# nixie_test_v1.net
KiCad netlist of a schematic drawn in EAGLE
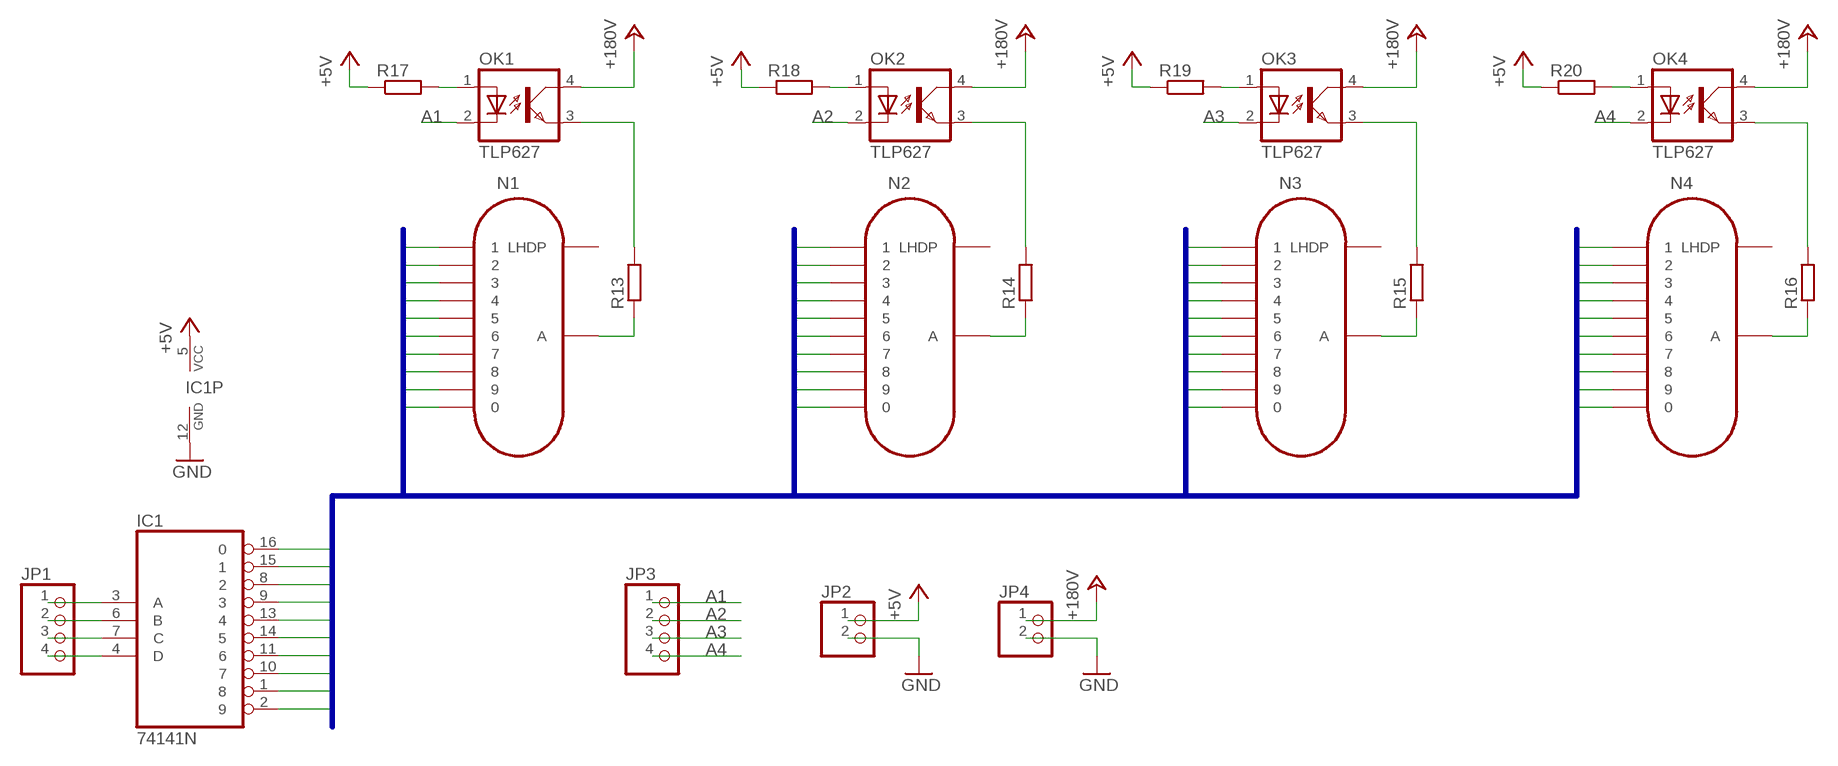
[diagram p0: schematic, sheet 1]

(export (version "E")
  (design (tool "Eeschema 10.0.6"))
  (components
    (comp (ref "IC1")
      (value "74141N")
      (footprint "eagle-import:DIL16")
      (libsource (lib "eagle-import") (part "74141N"))
    )
    (comp (ref "JP1")
      (value "PINHD-1X4")
      (footprint "eagle-import:1X04")
      (libsource (lib "eagle-import") (part "PINHD-1X4"))
    )
    (comp (ref "JP2")
      (value "PINHD-1X2")
      (footprint "eagle-import:1X02")
      (libsource (lib "eagle-import") (part "PINHD-1X2"))
    )
    (comp (ref "JP3")
      (value "PINHD-1X4")
      (footprint "eagle-import:1X04")
      (libsource (lib "eagle-import") (part "PINHD-1X4"))
    )
    (comp (ref "JP4")
      (value "PINHD-1X2")
      (footprint "eagle-import:1X02")
      (libsource (lib "eagle-import") (part "PINHD-1X2"))
    )
    (comp (ref "N1")
      (value "IN-12B")
      (footprint "eagle-import:IN-12")
      (libsource (lib "eagle-import") (part "IN-12B"))
    )
    (comp (ref "N2")
      (value "IN-12B")
      (footprint "eagle-import:IN-12")
      (libsource (lib "eagle-import") (part "IN-12B"))
    )
    (comp (ref "N3")
      (value "IN-12B")
      (footprint "eagle-import:IN-12")
      (libsource (lib "eagle-import") (part "IN-12B"))
    )
    (comp (ref "N4")
      (value "IN-12B")
      (footprint "eagle-import:IN-12")
      (libsource (lib "eagle-import") (part "IN-12B"))
    )
    (comp (ref "OK1")
      (value "TLP627")
      (footprint "eagle-import:4-SMD")
      (libsource (lib "eagle-import") (part "TLP627"))
    )
    (comp (ref "OK2")
      (value "TLP627")
      (footprint "eagle-import:4-SMD")
      (libsource (lib "eagle-import") (part "TLP627"))
    )
    (comp (ref "OK3")
      (value "TLP627")
      (footprint "eagle-import:4-SMD")
      (libsource (lib "eagle-import") (part "TLP627"))
    )
    (comp (ref "OK4")
      (value "TLP627")
      (footprint "eagle-import:4-SMD")
      (libsource (lib "eagle-import") (part "TLP627"))
    )
    (comp (ref "R13")
      (value "R-EU_10")
      (footprint "eagle-import:0207_10")
      (libsource (lib "eagle-import") (part "R-EU_10"))
    )
    (comp (ref "R14")
      (value "R-EU_10")
      (footprint "eagle-import:0207_10")
      (libsource (lib "eagle-import") (part "R-EU_10"))
    )
    (comp (ref "R15")
      (value "R-EU_10")
      (footprint "eagle-import:0207_10")
      (libsource (lib "eagle-import") (part "R-EU_10"))
    )
    (comp (ref "R16")
      (value "R-EU_10")
      (footprint "eagle-import:0207_10")
      (libsource (lib "eagle-import") (part "R-EU_10"))
    )
    (comp (ref "R17")
      (value "R-EU_10")
      (footprint "eagle-import:0207_10")
      (libsource (lib "eagle-import") (part "R-EU_10"))
    )
    (comp (ref "R18")
      (value "R-EU_10")
      (footprint "eagle-import:0207_10")
      (libsource (lib "eagle-import") (part "R-EU_10"))
    )
    (comp (ref "R19")
      (value "R-EU_10")
      (footprint "eagle-import:0207_10")
      (libsource (lib "eagle-import") (part "R-EU_10"))
    )
    (comp (ref "R20")
      (value "R-EU_10")
      (footprint "eagle-import:0207_10")
      (libsource (lib "eagle-import") (part "R-EU_10"))
    )
  )
  (nets
    (net (code "1") (name "+5V") (class "Default")
      (node (ref "IC1") (pin "5") (pinfunction "VCC_5") (pintype "power_in"))
      (node (ref "JP2") (pin "1") (pinfunction "1_1") (pintype "passive"))
      (node (ref "R17") (pin "1") (pinfunction "1_1") (pintype "passive"))
      (node (ref "R18") (pin "1") (pinfunction "1_1") (pintype "passive"))
      (node (ref "R19") (pin "1") (pinfunction "1_1") (pintype "passive"))
      (node (ref "R20") (pin "1") (pinfunction "1_1") (pintype "passive"))
    )
    (net (code "2") (name "+180V") (class "Default")
      (node (ref "JP4") (pin "1") (pinfunction "1_1") (pintype "passive"))
      (node (ref "OK1") (pin "4") (pinfunction "COL_4") (pintype "passive"))
      (node (ref "OK2") (pin "4") (pinfunction "COL_4") (pintype "passive"))
      (node (ref "OK3") (pin "4") (pinfunction "COL_4") (pintype "passive"))
      (node (ref "OK4") (pin "4") (pinfunction "COL_4") (pintype "passive"))
    )
    (net (code "3") (name "/A1") (class "Default")
      (node (ref "JP3") (pin "1") (pinfunction "1_1") (pintype "passive"))
      (node (ref "OK1") (pin "2") (pinfunction "C_2") (pintype "passive"))
    )
    (net (code "4") (name "/A2") (class "Default")
      (node (ref "JP3") (pin "2") (pinfunction "2_2") (pintype "passive"))
      (node (ref "OK2") (pin "2") (pinfunction "C_2") (pintype "passive"))
    )
    (net (code "5") (name "/A3") (class "Default")
      (node (ref "JP3") (pin "3") (pinfunction "3_3") (pintype "passive"))
      (node (ref "OK3") (pin "2") (pinfunction "C_2") (pintype "passive"))
    )
    (net (code "6") (name "/A4") (class "Default")
      (node (ref "JP3") (pin "4") (pinfunction "4_4") (pintype "passive"))
      (node (ref "OK4") (pin "2") (pinfunction "C_2") (pintype "passive"))
    )
    (net (code "7") (name "/C0") (class "Default")
      (node (ref "IC1") (pin "16") (pinfunction "0_16") (pintype "open_collector"))
      (node (ref "N1") (pin "0") (pinfunction "0_0") (pintype "bidirectional"))
      (node (ref "N2") (pin "0") (pinfunction "0_0") (pintype "bidirectional"))
      (node (ref "N3") (pin "0") (pinfunction "0_0") (pintype "bidirectional"))
      (node (ref "N4") (pin "0") (pinfunction "0_0") (pintype "bidirectional"))
    )
    (net (code "8") (name "/C1") (class "Default")
      (node (ref "IC1") (pin "15") (pinfunction "1_15") (pintype "open_collector"))
      (node (ref "N1") (pin "1") (pinfunction "1_1") (pintype "bidirectional"))
      (node (ref "N2") (pin "1") (pinfunction "1_1") (pintype "bidirectional"))
      (node (ref "N3") (pin "1") (pinfunction "1_1") (pintype "bidirectional"))
      (node (ref "N4") (pin "1") (pinfunction "1_1") (pintype "bidirectional"))
    )
    (net (code "9") (name "/C2") (class "Default")
      (node (ref "IC1") (pin "8") (pinfunction "2_8") (pintype "open_collector"))
      (node (ref "N1") (pin "2") (pinfunction "2_2") (pintype "bidirectional"))
      (node (ref "N2") (pin "2") (pinfunction "2_2") (pintype "bidirectional"))
      (node (ref "N3") (pin "2") (pinfunction "2_2") (pintype "bidirectional"))
      (node (ref "N4") (pin "2") (pinfunction "2_2") (pintype "bidirectional"))
    )
    (net (code "10") (name "/C3") (class "Default")
      (node (ref "IC1") (pin "9") (pinfunction "3_9") (pintype "open_collector"))
      (node (ref "N1") (pin "3") (pinfunction "3_3") (pintype "bidirectional"))
      (node (ref "N2") (pin "3") (pinfunction "3_3") (pintype "bidirectional"))
      (node (ref "N3") (pin "3") (pinfunction "3_3") (pintype "bidirectional"))
      (node (ref "N4") (pin "3") (pinfunction "3_3") (pintype "bidirectional"))
    )
    (net (code "11") (name "/C4") (class "Default")
      (node (ref "IC1") (pin "13") (pinfunction "4_13") (pintype "open_collector"))
      (node (ref "N1") (pin "4") (pinfunction "4_4") (pintype "bidirectional"))
      (node (ref "N2") (pin "4") (pinfunction "4_4") (pintype "bidirectional"))
      (node (ref "N3") (pin "4") (pinfunction "4_4") (pintype "bidirectional"))
      (node (ref "N4") (pin "4") (pinfunction "4_4") (pintype "bidirectional"))
    )
    (net (code "12") (name "/C5") (class "Default")
      (node (ref "IC1") (pin "14") (pinfunction "5_14") (pintype "open_collector"))
      (node (ref "N1") (pin "5") (pinfunction "5_5") (pintype "bidirectional"))
      (node (ref "N2") (pin "5") (pinfunction "5_5") (pintype "bidirectional"))
      (node (ref "N3") (pin "5") (pinfunction "5_5") (pintype "bidirectional"))
      (node (ref "N4") (pin "5") (pinfunction "5_5") (pintype "bidirectional"))
    )
    (net (code "13") (name "/C6") (class "Default")
      (node (ref "IC1") (pin "11") (pinfunction "6_11") (pintype "open_collector"))
      (node (ref "N1") (pin "6") (pinfunction "6_6") (pintype "bidirectional"))
      (node (ref "N2") (pin "6") (pinfunction "6_6") (pintype "bidirectional"))
      (node (ref "N3") (pin "6") (pinfunction "6_6") (pintype "bidirectional"))
      (node (ref "N4") (pin "6") (pinfunction "6_6") (pintype "bidirectional"))
    )
    (net (code "14") (name "/C7") (class "Default")
      (node (ref "IC1") (pin "10") (pinfunction "7_10") (pintype "open_collector"))
      (node (ref "N1") (pin "7") (pinfunction "7_7") (pintype "bidirectional"))
      (node (ref "N2") (pin "7") (pinfunction "7_7") (pintype "bidirectional"))
      (node (ref "N3") (pin "7") (pinfunction "7_7") (pintype "bidirectional"))
      (node (ref "N4") (pin "7") (pinfunction "7_7") (pintype "bidirectional"))
    )
    (net (code "15") (name "/C8") (class "Default")
      (node (ref "IC1") (pin "1") (pinfunction "8_1") (pintype "open_collector"))
      (node (ref "N1") (pin "8") (pinfunction "8_8") (pintype "bidirectional"))
      (node (ref "N2") (pin "8") (pinfunction "8_8") (pintype "bidirectional"))
      (node (ref "N3") (pin "8") (pinfunction "8_8") (pintype "bidirectional"))
      (node (ref "N4") (pin "8") (pinfunction "8_8") (pintype "bidirectional"))
    )
    (net (code "16") (name "/C9") (class "Default")
      (node (ref "IC1") (pin "2") (pinfunction "9_2") (pintype "open_collector"))
      (node (ref "N1") (pin "9") (pinfunction "9_9") (pintype "bidirectional"))
      (node (ref "N2") (pin "9") (pinfunction "9_9") (pintype "bidirectional"))
      (node (ref "N3") (pin "9") (pinfunction "9_9") (pintype "bidirectional"))
      (node (ref "N4") (pin "9") (pinfunction "9_9") (pintype "bidirectional"))
    )
    (net (code "17") (name "GND") (class "Default")
      (node (ref "IC1") (pin "12") (pinfunction "GND_12") (pintype "power_in"))
      (node (ref "JP2") (pin "2") (pinfunction "2_2") (pintype "passive"))
      (node (ref "JP4") (pin "2") (pinfunction "2_2") (pintype "passive"))
    )
    (net (code "18") (name "Net-(IC1A-A)") (class "Default")
      (node (ref "IC1") (pin "3") (pinfunction "A_3") (pintype "input"))
      (node (ref "JP1") (pin "1") (pinfunction "1_1") (pintype "passive"))
    )
    (net (code "19") (name "Net-(IC1A-B)") (class "Default")
      (node (ref "IC1") (pin "6") (pinfunction "B_6") (pintype "input"))
      (node (ref "JP1") (pin "2") (pinfunction "2_2") (pintype "passive"))
    )
    (net (code "20") (name "Net-(IC1A-C)") (class "Default")
      (node (ref "IC1") (pin "7") (pinfunction "C_7") (pintype "input"))
      (node (ref "JP1") (pin "3") (pinfunction "3_3") (pintype "passive"))
    )
    (net (code "21") (name "Net-(IC1A-D)") (class "Default")
      (node (ref "IC1") (pin "4") (pinfunction "D_4") (pintype "input"))
      (node (ref "JP1") (pin "4") (pinfunction "4_4") (pintype "passive"))
    )
    (net (code "22") (name "Net-(N1-PadA)") (class "Default")
      (node (ref "N1") (pin "A") (pinfunction "A_A") (pintype "bidirectional"))
      (node (ref "R13") (pin "1") (pinfunction "1_1") (pintype "passive"))
    )
    (net (code "23") (name "Net-(N2-PadA)") (class "Default")
      (node (ref "N2") (pin "A") (pinfunction "A_A") (pintype "bidirectional"))
      (node (ref "R14") (pin "1") (pinfunction "1_1") (pintype "passive"))
    )
    (net (code "24") (name "Net-(N3-PadA)") (class "Default")
      (node (ref "N3") (pin "A") (pinfunction "A_A") (pintype "bidirectional"))
      (node (ref "R15") (pin "1") (pinfunction "1_1") (pintype "passive"))
    )
    (net (code "25") (name "Net-(N4-PadA)") (class "Default")
      (node (ref "N4") (pin "A") (pinfunction "A_A") (pintype "bidirectional"))
      (node (ref "R16") (pin "1") (pinfunction "1_1") (pintype "passive"))
    )
    (net (code "26") (name "Net-(OK1-A)") (class "Default")
      (node (ref "OK1") (pin "1") (pinfunction "A_1") (pintype "passive"))
      (node (ref "R17") (pin "2") (pinfunction "2_2") (pintype "passive"))
    )
    (net (code "27") (name "Net-(OK1-EMIT)") (class "Default")
      (node (ref "OK1") (pin "3") (pinfunction "EMIT_3") (pintype "passive"))
      (node (ref "R13") (pin "2") (pinfunction "2_2") (pintype "passive"))
    )
    (net (code "28") (name "Net-(OK2-A)") (class "Default")
      (node (ref "OK2") (pin "1") (pinfunction "A_1") (pintype "passive"))
      (node (ref "R18") (pin "2") (pinfunction "2_2") (pintype "passive"))
    )
    (net (code "29") (name "Net-(OK2-EMIT)") (class "Default")
      (node (ref "OK2") (pin "3") (pinfunction "EMIT_3") (pintype "passive"))
      (node (ref "R14") (pin "2") (pinfunction "2_2") (pintype "passive"))
    )
    (net (code "30") (name "Net-(OK3-A)") (class "Default")
      (node (ref "OK3") (pin "1") (pinfunction "A_1") (pintype "passive"))
      (node (ref "R19") (pin "2") (pinfunction "2_2") (pintype "passive"))
    )
    (net (code "31") (name "Net-(OK3-EMIT)") (class "Default")
      (node (ref "OK3") (pin "3") (pinfunction "EMIT_3") (pintype "passive"))
      (node (ref "R15") (pin "2") (pinfunction "2_2") (pintype "passive"))
    )
    (net (code "32") (name "Net-(OK4-A)") (class "Default")
      (node (ref "OK4") (pin "1") (pinfunction "A_1") (pintype "passive"))
      (node (ref "R20") (pin "2") (pinfunction "2_2") (pintype "passive"))
    )
    (net (code "33") (name "Net-(OK4-EMIT)") (class "Default")
      (node (ref "OK4") (pin "3") (pinfunction "EMIT_3") (pintype "passive"))
      (node (ref "R16") (pin "2") (pinfunction "2_2") (pintype "passive"))
    )
    (net (code "34") (name "unconnected-(N1-PadLHDP)") (class "Default")
      (node (ref "N1") (pin "LHDP") (pinfunction "LHDP_LHDP") (pintype "bidirectional"))
    )
    (net (code "35") (name "unconnected-(N2-PadLHDP)") (class "Default")
      (node (ref "N2") (pin "LHDP") (pinfunction "LHDP_LHDP") (pintype "bidirectional"))
    )
    (net (code "36") (name "unconnected-(N3-PadLHDP)") (class "Default")
      (node (ref "N3") (pin "LHDP") (pinfunction "LHDP_LHDP") (pintype "bidirectional"))
    )
    (net (code "37") (name "unconnected-(N4-PadLHDP)") (class "Default")
      (node (ref "N4") (pin "LHDP") (pinfunction "LHDP_LHDP") (pintype "bidirectional"))
    )
  )
)
